# stacja_meteo_v3.net
KiCad netlist of a schematic drawn in EAGLE
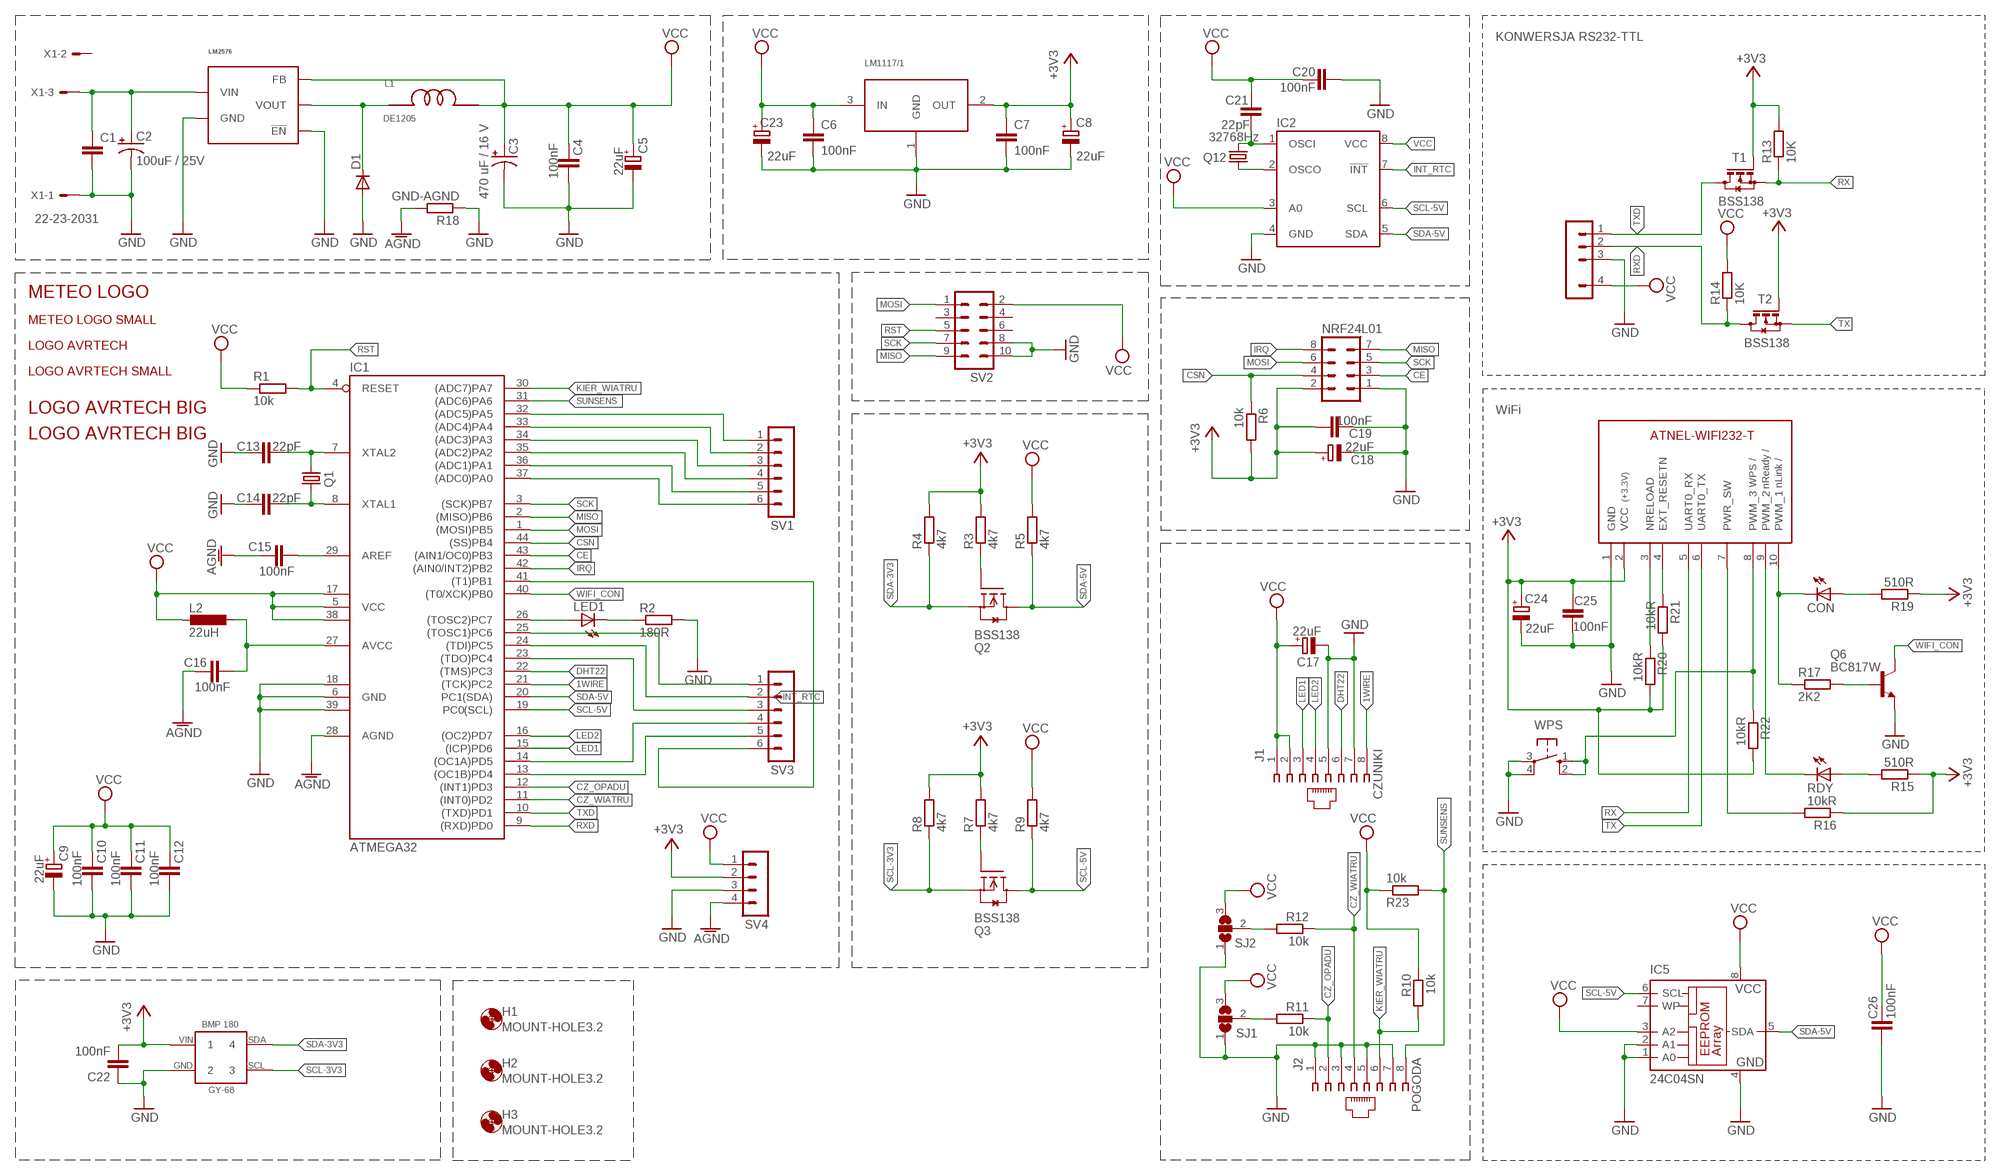
[diagram p0: schematic, sheet 1]

(export (version "E")
  (design (tool "Eeschema 10.0.6"))
  (components
    (comp (ref "BMP1")
      (value "GY-68")
      (footprint "eagle-import:GY-68")
      (libsource (lib "eagle-import") (part "GY-68"))
    )
    (comp (ref "C1")
      (value "C-EUC1206")
      (footprint "eagle-import:C1206")
      (libsource (lib "eagle-import") (part "C-EUC1206"))
    )
    (comp (ref "C2")
      (value "100uF / 25V")
      (footprint "eagle-import:PANASONIC_D")
      (libsource (lib "eagle-import") (part "CAP_POLD"))
    )
    (comp (ref "C3")
      (value "470 uF / 16 V")
      (footprint "eagle-import:PANASONIC_E")
      (libsource (lib "eagle-import") (part "CAP_POLE"))
    )
    (comp (ref "C4")
      (value "100nF")
      (footprint "eagle-import:C1206")
      (libsource (lib "eagle-import") (part "C-EUC1206"))
    )
    (comp (ref "C5")
      (value "22uF")
      (footprint "eagle-import:SMC_A")
      (libsource (lib "eagle-import") (part "CPOL-EUSMCA"))
    )
    (comp (ref "C6")
      (value "100nF")
      (footprint "eagle-import:C0805")
      (libsource (lib "eagle-import") (part "C-EUC0805"))
    )
    (comp (ref "C7")
      (value "100nF")
      (footprint "eagle-import:C0805")
      (libsource (lib "eagle-import") (part "C-EUC0805"))
    )
    (comp (ref "C8")
      (value "22uF")
      (footprint "eagle-import:SMC_A")
      (libsource (lib "eagle-import") (part "CPOL-EUSMCA"))
    )
    (comp (ref "C9")
      (value "22uF")
      (footprint "eagle-import:SMC_A")
      (libsource (lib "eagle-import") (part "CPOL-EUSMCA"))
    )
    (comp (ref "C10")
      (value "100nF")
      (footprint "eagle-import:C1206")
      (libsource (lib "eagle-import") (part "C-EUC1206"))
    )
    (comp (ref "C11")
      (value "100nF")
      (footprint "eagle-import:C1206")
      (libsource (lib "eagle-import") (part "C-EUC1206"))
    )
    (comp (ref "C12")
      (value "100nF")
      (footprint "eagle-import:C1206")
      (libsource (lib "eagle-import") (part "C-EUC1206"))
    )
    (comp (ref "C13")
      (value "22pF")
      (footprint "eagle-import:C0805K")
      (libsource (lib "eagle-import") (part "C-EUC0805K"))
    )
    (comp (ref "C14")
      (value "22pF")
      (footprint "eagle-import:C0805K")
      (libsource (lib "eagle-import") (part "C-EUC0805K"))
    )
    (comp (ref "C15")
      (value "100nF")
      (footprint "eagle-import:C1206")
      (libsource (lib "eagle-import") (part "C-EUC1206"))
    )
    (comp (ref "C16")
      (value "100nF")
      (footprint "eagle-import:C1206")
      (libsource (lib "eagle-import") (part "C-EUC1206"))
    )
    (comp (ref "C17")
      (value "22uF")
      (footprint "eagle-import:SMC_A")
      (libsource (lib "eagle-import") (part "CPOL-EUSMCA"))
    )
    (comp (ref "C18")
      (value "22uF")
      (footprint "eagle-import:SMC_A")
      (libsource (lib "eagle-import") (part "CPOL-EUSMCA"))
    )
    (comp (ref "C19")
      (value "100nF")
      (footprint "eagle-import:C0805")
      (libsource (lib "eagle-import") (part "C-EUC0805"))
    )
    (comp (ref "C20")
      (value "100nF")
      (footprint "eagle-import:C1206K")
      (libsource (lib "eagle-import") (part "C-EUC1206K"))
    )
    (comp (ref "C21")
      (value "22pF")
      (footprint "eagle-import:C1206K")
      (libsource (lib "eagle-import") (part "C-EUC1206K"))
    )
    (comp (ref "C22")
      (value "100nF")
      (footprint "eagle-import:C1206")
      (libsource (lib "eagle-import") (part "C-EUC1206"))
    )
    (comp (ref "C23")
      (value "22uF")
      (footprint "eagle-import:SMC_A")
      (libsource (lib "eagle-import") (part "CPOL-EUSMCA"))
    )
    (comp (ref "C24")
      (value "22uF")
      (footprint "eagle-import:SMC_A")
      (libsource (lib "eagle-import") (part "CPOL-EUSMCA"))
    )
    (comp (ref "C25")
      (value "100nF")
      (footprint "eagle-import:C0805")
      (libsource (lib "eagle-import") (part "C-EUC0805"))
    )
    (comp (ref "C26")
      (value "100nF")
      (footprint "eagle-import:C1206K")
      (libsource (lib "eagle-import") (part "C-EUC1206K"))
    )
    (comp (ref "CON")
      (value "LEDSML0805")
      (footprint "eagle-import:SML0805")
      (libsource (lib "eagle-import") (part "LEDSML0805"))
    )
    (comp (ref "D1")
      (value "DIODE-SMC")
      (footprint "eagle-import:SMC")
      (libsource (lib "eagle-import") (part "DIODE-SMC"))
    )
    (comp (ref "H1")
      (value "MOUNT-HOLE3.2")
      (footprint "eagle-import:3,2")
      (libsource (lib "eagle-import") (part "MOUNT-HOLE3.2"))
    )
    (comp (ref "H2")
      (value "MOUNT-HOLE3.2")
      (footprint "eagle-import:3,2")
      (libsource (lib "eagle-import") (part "MOUNT-HOLE3.2"))
    )
    (comp (ref "H3")
      (value "MOUNT-HOLE3.2")
      (footprint "eagle-import:3,2")
      (libsource (lib "eagle-import") (part "MOUNT-HOLE3.2"))
    )
    (comp (ref "IC1")
      (value "ATMEGA32")
      (footprint "eagle-import:TQFP44")
      (libsource (lib "eagle-import") (part "MEGA32ORIGINAL"))
    )
    (comp (ref "IC2")
      (value "RTC_PCF8583T")
      (footprint "eagle-import:SO08")
      (libsource (lib "eagle-import") (part "RTC_PCF8583T"))
    )
    (comp (ref "IC5")
      (value "24C04SN")
      (footprint "eagle-import:SO-08")
      (fields (field (name "MPN") "M24C04-WMN6P"))
      (libsource (lib "eagle-import") (part "24CSN04"))
    )
    (comp (ref "J1")
      (value "CZUNIKI")
      (footprint "eagle-import:556416-1")
      (libsource (lib "eagle-import") (part "556416-1"))
    )
    (comp (ref "J2")
      (value "POGODA")
      (footprint "eagle-import:556416-1")
      (libsource (lib "eagle-import") (part "556416-1"))
    )
    (comp (ref "L1")
      (value "DE1205")
      (footprint "eagle-import:DE1205")
      (libsource (lib "eagle-import") (part "DE1205"))
    )
    (comp (ref "L2")
      (value "22uH")
      (footprint "eagle-import:IR-2")
      (libsource (lib "eagle-import") (part "L-EUIR-2"))
    )
    (comp (ref "LED1")
      (value "LED5MM")
      (footprint "eagle-import:LED5MM")
      (libsource (lib "eagle-import") (part "LED5MM"))
    )
    (comp (ref "LM1117/1")
      (value "LM1117-3.3")
      (footprint "eagle-import:SOT223")
      (libsource (lib "eagle-import") (part "LM1117-3.3"))
    )
    (comp (ref "LM2576")
      (value "LM2576D2PAK-5")
      (footprint "eagle-import:D2PAK-5")
      (libsource (lib "eagle-import") (part "LM2576D2PAK-5"))
    )
    (comp (ref "NRF24L01")
      (value "ML10")
      (footprint "eagle-import:ML10")
      (libsource (lib "eagle-import") (part "ML10"))
    )
    (comp (ref "Q1")
      (value "11.059 MHz")
      (footprint "eagle-import:CSM-7X-DU")
      (libsource (lib "eagle-import") (part "CSM-7X-DU"))
    )
    (comp (ref "Q2")
      (value "BSS138")
      (footprint "eagle-import:SOT23")
      (libsource (lib "eagle-import") (part "BSS138"))
    )
    (comp (ref "Q3")
      (value "BSS138")
      (footprint "eagle-import:SOT23")
      (libsource (lib "eagle-import") (part "BSS138"))
    )
    (comp (ref "Q6")
      (value "BC817W")
      (footprint "eagle-import:SOT23-BEC")
      (libsource (lib "eagle-import") (part "BC817SMD-16LT1"))
    )
    (comp (ref "Q12")
      (value "32768Hz")
      (footprint "eagle-import:MC-406")
      (fields (field (name "MF") "BANNER ENGINEERING CORPORATION") (field (name "MPN") "MQDMC-406"))
      (libsource (lib "eagle-import") (part "MC-406"))
    )
    (comp (ref "R1")
      (value "10k")
      (footprint "eagle-import:R0603")
      (libsource (lib "eagle-import") (part "R-EU_R0603"))
    )
    (comp (ref "R2")
      (value "180R")
      (footprint "eagle-import:R0805")
      (libsource (lib "eagle-import") (part "R-EU_R0805"))
    )
    (comp (ref "R3")
      (value "4k7")
      (footprint "eagle-import:R0805")
      (libsource (lib "eagle-import") (part "R-EU_R0805"))
    )
    (comp (ref "R4")
      (value "4k7")
      (footprint "eagle-import:R0805")
      (libsource (lib "eagle-import") (part "R-EU_R0805"))
    )
    (comp (ref "R5")
      (value "4k7")
      (footprint "eagle-import:R0805")
      (libsource (lib "eagle-import") (part "R-EU_R0805"))
    )
    (comp (ref "R6")
      (value "10k")
      (footprint "eagle-import:R0805W")
      (libsource (lib "eagle-import") (part "R-EU_R0805W"))
    )
    (comp (ref "R7")
      (value "4k7")
      (footprint "eagle-import:R0805")
      (libsource (lib "eagle-import") (part "R-EU_R0805"))
    )
    (comp (ref "R8")
      (value "4k7")
      (footprint "eagle-import:R0805")
      (libsource (lib "eagle-import") (part "R-EU_R0805"))
    )
    (comp (ref "R9")
      (value "4k7")
      (footprint "eagle-import:R0805")
      (libsource (lib "eagle-import") (part "R-EU_R0805"))
    )
    (comp (ref "R10")
      (value "10k")
      (footprint "eagle-import:R0603")
      (libsource (lib "eagle-import") (part "R-EU_R0603"))
    )
    (comp (ref "R11")
      (value "10k")
      (footprint "eagle-import:R0603")
      (libsource (lib "eagle-import") (part "R-EU_R0603"))
    )
    (comp (ref "R12")
      (value "10k")
      (footprint "eagle-import:R0603")
      (libsource (lib "eagle-import") (part "R-EU_R0603"))
    )
    (comp (ref "R13")
      (value "10K")
      (footprint "eagle-import:R0805")
      (libsource (lib "eagle-import") (part "resistor_R-EU_R0805"))
    )
    (comp (ref "R14")
      (value "10K")
      (footprint "eagle-import:R0805")
      (libsource (lib "eagle-import") (part "resistor_R-EU_R0805"))
    )
    (comp (ref "R15")
      (value "510R")
      (footprint "eagle-import:R0603")
      (libsource (lib "eagle-import") (part "R-EU_R0603"))
    )
    (comp (ref "R16")
      (value "10kR")
      (footprint "eagle-import:R0603")
      (libsource (lib "eagle-import") (part "R-EU_R0603"))
    )
    (comp (ref "R17")
      (value "2K2")
      (footprint "eagle-import:R0603")
      (libsource (lib "eagle-import") (part "R-EU_R0603"))
    )
    (comp (ref "R18")
      (value "GND-AGND")
      (footprint "eagle-import:R0805")
      (libsource (lib "eagle-import") (part "R-EU_R0805"))
    )
    (comp (ref "R19")
      (value "510R")
      (footprint "eagle-import:R0603")
      (libsource (lib "eagle-import") (part "R-EU_R0603"))
    )
    (comp (ref "R20")
      (value "10kR")
      (footprint "eagle-import:R0603")
      (libsource (lib "eagle-import") (part "R-EU_R0603"))
    )
    (comp (ref "R21")
      (value "10kR")
      (footprint "eagle-import:R0603")
      (libsource (lib "eagle-import") (part "R-EU_R0603"))
    )
    (comp (ref "R22")
      (value "10kR")
      (footprint "eagle-import:R0603")
      (libsource (lib "eagle-import") (part "R-EU_R0603"))
    )
    (comp (ref "R23")
      (value "10k")
      (footprint "eagle-import:R0603")
      (libsource (lib "eagle-import") (part "R-EU_R0603"))
    )
    (comp (ref "RDY")
      (value "LEDSML0805")
      (footprint "eagle-import:SML0805")
      (libsource (lib "eagle-import") (part "LEDSML0805"))
    )
    (comp (ref "RS232-TTL")
      (value "ATB-BTM-222")
      (footprint "eagle-import:ATB-BTM-222")
      (libsource (lib "eagle-import") (part "ATB-BTM-222"))
    )
    (comp (ref "SJ1")
      (value "SJ2W")
      (footprint "eagle-import:SJ_2")
      (libsource (lib "eagle-import") (part "SJ2W"))
    )
    (comp (ref "SJ2")
      (value "SJ2W")
      (footprint "eagle-import:SJ_2")
      (libsource (lib "eagle-import") (part "SJ2W"))
    )
    (comp (ref "SV1")
      (value "MA06-1")
      (footprint "eagle-import:MA06-1")
      (libsource (lib "eagle-import") (part "MA06-1"))
    )
    (comp (ref "SV2")
      (value "ML10")
      (footprint "eagle-import:ML10")
      (libsource (lib "eagle-import") (part "con-harting-ml_ML10"))
    )
    (comp (ref "SV3")
      (value "MA06-1")
      (footprint "eagle-import:MA06-1")
      (libsource (lib "eagle-import") (part "MA06-1"))
    )
    (comp (ref "SV4")
      (value "MA04-1")
      (footprint "eagle-import:MA04-1")
      (libsource (lib "eagle-import") (part "MA04-1"))
    )
    (comp (ref "T1")
      (value "BSS138")
      (footprint "eagle-import:SOT23")
      (libsource (lib "eagle-import") (part "BSS123"))
    )
    (comp (ref "T2")
      (value "BSS138")
      (footprint "eagle-import:SOT23")
      (libsource (lib "eagle-import") (part "BSS123"))
    )
    (comp (ref "U$2")
      (value "ATNEL-WIFI232-T_2")
      (footprint "eagle-import:ATNEL-WIFI232-T_2")
      (libsource (lib "eagle-import") (part "ATNEL-WIFI232-T_2"))
    )
    (comp (ref "U$3")
      (value "METEO_LOGO")
      (footprint "eagle-import:LOGO_METEO")
      (libsource (lib "eagle-import") (part "METEO_LOGO"))
    )
    (comp (ref "U$4")
      (value "METEO_LOGO_SMALL")
      (footprint "eagle-import:LOGO_METEO_SMALL")
      (libsource (lib "eagle-import") (part "METEO_LOGO_SMALL"))
    )
    (comp (ref "U$6")
      (value "LOGO_AVRTECH")
      (footprint "eagle-import:LOGO_AVRTECH")
      (libsource (lib "eagle-import") (part "LOGO_AVRTECH"))
    )
    (comp (ref "U$7")
      (value "LOGO_AVRTECH_SMALL")
      (footprint "eagle-import:LOGO_AVRTECH_SMALL")
      (libsource (lib "eagle-import") (part "LOGO_AVRTECH_SMALL"))
    )
    (comp (ref "U$8")
      (value "LOGO_AVRTECH_BIG")
      (footprint "eagle-import:LOGOAVRTECHBIG")
      (libsource (lib "eagle-import") (part "LOGO_AVRTECH_BIG"))
    )
    (comp (ref "U$9")
      (value "LOGO_AVRTECH_BIG")
      (footprint "eagle-import:LOGOAVRTECHBIG")
      (libsource (lib "eagle-import") (part "LOGO_AVRTECH_BIG"))
    )
    (comp (ref "WPS")
      (value "10-XX")
      (footprint "eagle-import:B3F-10XX")
      (fields (field (name "MPN") "B3F-1000"))
      (libsource (lib "eagle-import") (part "10-XX"))
    )
    (comp (ref "X1")
      (value "22-23-2031")
      (footprint "eagle-import:22-23-2031")
      (fields (field (name "MF") "MOLEX"))
      (libsource (lib "eagle-import") (part "22-23-2031"))
    )
  )
  (nets
    (net (code "1") (name "+3V3") (class "Default")
      (node (ref "BMP1") (pin "1") (pinfunction "1_1") (pintype "bidirectional"))
      (node (ref "C18") (pin "+") (pinfunction "+_+") (pintype "passive"))
      (node (ref "C19") (pin "1") (pinfunction "1_1") (pintype "passive"))
      (node (ref "C22") (pin "2") (pinfunction "2_2") (pintype "passive"))
      (node (ref "C24") (pin "+") (pinfunction "+_+") (pintype "passive"))
      (node (ref "C25") (pin "1") (pinfunction "1_1") (pintype "passive"))
      (node (ref "C7") (pin "1") (pinfunction "1_1") (pintype "passive"))
      (node (ref "C8") (pin "+") (pinfunction "+_+") (pintype "passive"))
      (node (ref "LM1117/1") (pin "2") (pinfunction "OUT_2") (pintype "bidirectional"))
      (node (ref "NRF24L01") (pin "2") (pinfunction "2_2") (pintype "passive"))
      (node (ref "R13") (pin "2") (pinfunction "2_2") (pintype "passive"))
      (node (ref "R15") (pin "1") (pinfunction "1_1") (pintype "passive"))
      (node (ref "R16") (pin "1") (pinfunction "1_1") (pintype "passive"))
      (node (ref "R19") (pin "1") (pinfunction "1_1") (pintype "passive"))
      (node (ref "R20") (pin "2") (pinfunction "2_2") (pintype "passive"))
      (node (ref "R21") (pin "2") (pinfunction "2_2") (pintype "passive"))
      (node (ref "R22") (pin "2") (pinfunction "2_2") (pintype "passive"))
      (node (ref "R3") (pin "2") (pinfunction "2_2") (pintype "passive"))
      (node (ref "R4") (pin "2") (pinfunction "2_2") (pintype "passive"))
      (node (ref "R6") (pin "2") (pinfunction "2_2") (pintype "passive"))
      (node (ref "R7") (pin "2") (pinfunction "2_2") (pintype "passive"))
      (node (ref "R8") (pin "2") (pinfunction "2_2") (pintype "passive"))
      (node (ref "SV4") (pin "2") (pinfunction "2_2") (pintype "passive"))
      (node (ref "T1") (pin "1") (pinfunction "G_1") (pintype "passive"))
      (node (ref "T2") (pin "1") (pinfunction "G_1") (pintype "passive"))
      (node (ref "U$2") (pin "2") (pinfunction "VCC_2") (pintype "bidirectional"))
    )
    (net (code "2") (name "1WIRE") (class "Default")
      (node (ref "IC1") (pin "21") (pinfunction "(TCK)PC2_21") (pintype "bidirectional"))
      (node (ref "J1") (pin "8") (pinfunction "8_8") (pintype "passive"))
    )
    (net (code "3") (name "AGND") (class "Default")
      (node (ref "C15") (pin "1") (pinfunction "1_1") (pintype "passive"))
      (node (ref "C16") (pin "1") (pinfunction "1_1") (pintype "passive"))
      (node (ref "IC1") (pin "28") (pinfunction "AGND_28") (pintype "power_in"))
      (node (ref "R18") (pin "2") (pinfunction "2_2") (pintype "passive"))
      (node (ref "SV4") (pin "4") (pinfunction "4_4") (pintype "passive"))
    )
    (net (code "4") (name "CE") (class "Default")
      (node (ref "IC1") (pin "43") (pinfunction "(AIN1/OC0)PB3_43") (pintype "bidirectional"))
      (node (ref "NRF24L01") (pin "3") (pinfunction "3_3") (pintype "passive"))
    )
    (net (code "5") (name "CSN") (class "Default")
      (node (ref "IC1") (pin "44") (pinfunction "(SS)PB4_44") (pintype "bidirectional"))
      (node (ref "NRF24L01") (pin "4") (pinfunction "4_4") (pintype "passive"))
      (node (ref "R6") (pin "1") (pinfunction "1_1") (pintype "passive"))
    )
    (net (code "6") (name "CZ_OPADU") (class "Default")
      (node (ref "IC1") (pin "12") (pinfunction "(INT1)PD3_12") (pintype "bidirectional"))
      (node (ref "J2") (pin "2") (pinfunction "2_2") (pintype "passive"))
      (node (ref "R11") (pin "1") (pinfunction "1_1") (pintype "passive"))
    )
    (net (code "7") (name "CZ_WIATRU") (class "Default")
      (node (ref "IC1") (pin "11") (pinfunction "(INT0)PD2_11") (pintype "bidirectional"))
      (node (ref "J2") (pin "4") (pinfunction "4_4") (pintype "passive"))
      (node (ref "R12") (pin "1") (pinfunction "1_1") (pintype "passive"))
    )
    (net (code "8") (name "DHT22") (class "Default")
      (node (ref "IC1") (pin "22") (pinfunction "(TMS)PC3_22") (pintype "bidirectional"))
      (node (ref "J1") (pin "6") (pinfunction "6_6") (pintype "passive"))
    )
    (net (code "9") (name "GND") (class "Default")
      (node (ref "BMP1") (pin "2") (pinfunction "2_2") (pintype "bidirectional"))
      (node (ref "C1") (pin "2") (pinfunction "2_2") (pintype "passive"))
      (node (ref "C10") (pin "2") (pinfunction "2_2") (pintype "passive"))
      (node (ref "C11") (pin "2") (pinfunction "2_2") (pintype "passive"))
      (node (ref "C12") (pin "2") (pinfunction "2_2") (pintype "passive"))
      (node (ref "C13") (pin "1") (pinfunction "1_1") (pintype "passive"))
      (node (ref "C14") (pin "1") (pinfunction "1_1") (pintype "passive"))
      (node (ref "C17") (pin "-") (pinfunction "-_-") (pintype "passive"))
      (node (ref "C18") (pin "-") (pinfunction "-_-") (pintype "passive"))
      (node (ref "C19") (pin "2") (pinfunction "2_2") (pintype "passive"))
      (node (ref "C2") (pin "-") (pinfunction "-_-") (pintype "passive"))
      (node (ref "C20") (pin "2") (pinfunction "2_2") (pintype "passive"))
      (node (ref "C22") (pin "1") (pinfunction "1_1") (pintype "passive"))
      (node (ref "C23") (pin "-") (pinfunction "-_-") (pintype "passive"))
      (node (ref "C24") (pin "-") (pinfunction "-_-") (pintype "passive"))
      (node (ref "C25") (pin "2") (pinfunction "2_2") (pintype "passive"))
      (node (ref "C26") (pin "2") (pinfunction "2_2") (pintype "passive"))
      (node (ref "C3") (pin "-") (pinfunction "-_-") (pintype "passive"))
      (node (ref "C4") (pin "2") (pinfunction "2_2") (pintype "passive"))
      (node (ref "C5") (pin "-") (pinfunction "-_-") (pintype "passive"))
      (node (ref "C6") (pin "2") (pinfunction "2_2") (pintype "passive"))
      (node (ref "C7") (pin "2") (pinfunction "2_2") (pintype "passive"))
      (node (ref "C8") (pin "-") (pinfunction "-_-") (pintype "passive"))
      (node (ref "C9") (pin "-") (pinfunction "-_-") (pintype "passive"))
      (node (ref "D1") (pin "A") (pinfunction "A_A") (pintype "passive"))
      (node (ref "IC1") (pin "18") (pinfunction "GND1_18") (pintype "power_in"))
      (node (ref "IC1") (pin "39") (pinfunction "GND2_39") (pintype "power_in"))
      (node (ref "IC1") (pin "6") (pinfunction "GND_6") (pintype "power_in"))
      (node (ref "IC2") (pin "4") (pinfunction "GND_4") (pintype "power_in"))
      (node (ref "IC5") (pin "1") (pinfunction "A0_1") (pintype "input"))
      (node (ref "IC5") (pin "2") (pinfunction "A1_2") (pintype "input"))
      (node (ref "IC5") (pin "4") (pinfunction "GND_4") (pintype "power_in"))
      (node (ref "J1") (pin "5") (pinfunction "5_5") (pintype "passive"))
      (node (ref "J1") (pin "7") (pinfunction "7_7") (pintype "passive"))
      (node (ref "J2") (pin "1") (pinfunction "1_1") (pintype "passive"))
      (node (ref "J2") (pin "3") (pinfunction "3_3") (pintype "passive"))
      (node (ref "J2") (pin "5") (pinfunction "5_5") (pintype "passive"))
      (node (ref "J2") (pin "7") (pinfunction "7_7") (pintype "passive"))
      (node (ref "LM1117/1") (pin "1") (pinfunction "GND_1") (pintype "bidirectional"))
      (node (ref "LM2576") (pin "P$3") (pinfunction "GND_P$3") (pintype "bidirectional"))
      (node (ref "LM2576") (pin "P$5") (pinfunction "~{EN}_P$5") (pintype "bidirectional"))
      (node (ref "LM2576") (pin "P$6") (pinfunction "GND_P$6") (pintype "bidirectional"))
      (node (ref "NRF24L01") (pin "1") (pinfunction "1_1") (pintype "passive"))
      (node (ref "Q6") (pin "E") (pinfunction "E_E") (pintype "passive"))
      (node (ref "R18") (pin "1") (pinfunction "1_1") (pintype "passive"))
      (node (ref "R2") (pin "2") (pinfunction "2_2") (pintype "passive"))
      (node (ref "RS232-TTL") (pin "3") (pinfunction "GND_3") (pintype "passive"))
      (node (ref "SJ1") (pin "1") (pinfunction "1_1") (pintype "passive"))
      (node (ref "SJ2") (pin "1") (pinfunction "1_1") (pintype "passive"))
      (node (ref "SV2") (pin "10") (pinfunction "10_10") (pintype "passive"))
      (node (ref "SV2") (pin "8") (pinfunction "8_8") (pintype "passive"))
      (node (ref "SV4") (pin "3") (pinfunction "3_3") (pintype "passive"))
      (node (ref "U$2") (pin "1") (pinfunction "GND_1") (pintype "bidirectional"))
      (node (ref "WPS") (pin "3") (pinfunction "P_3") (pintype "passive"))
      (node (ref "WPS") (pin "4") (pinfunction "P1_4") (pintype "passive"))
      (node (ref "X1") (pin "1") (pinfunction "S_1") (pintype "passive"))
    )
    (net (code "10") (name "INT_RTC") (class "Default")
      (node (ref "IC1") (pin "24") (pinfunction "(TDI)PC5_24") (pintype "bidirectional"))
      (node (ref "IC2") (pin "7") (pinfunction "~{INT}_7") (pintype "output"))
      (node (ref "SV3") (pin "2") (pinfunction "2_2") (pintype "passive"))
    )
    (net (code "11") (name "IRQ") (class "Default")
      (node (ref "IC1") (pin "42") (pinfunction "(AIN0/INT2)PB2_42") (pintype "bidirectional"))
      (node (ref "NRF24L01") (pin "8") (pinfunction "8_8") (pintype "passive"))
    )
    (net (code "12") (name "KIER_WIATRU") (class "Default")
      (node (ref "IC1") (pin "30") (pinfunction "(ADC7)PA7_30") (pintype "bidirectional"))
      (node (ref "J2") (pin "6") (pinfunction "6_6") (pintype "passive"))
      (node (ref "R10") (pin "2") (pinfunction "2_2") (pintype "passive"))
    )
    (net (code "13") (name "LED1") (class "Default")
      (node (ref "IC1") (pin "15") (pinfunction "(ICP)PD6_15") (pintype "bidirectional"))
      (node (ref "J1") (pin "3") (pinfunction "3_3") (pintype "passive"))
    )
    (net (code "14") (name "LED2") (class "Default")
      (node (ref "IC1") (pin "16") (pinfunction "(OC2)PD7_16") (pintype "bidirectional"))
      (node (ref "J1") (pin "4") (pinfunction "4_4") (pintype "passive"))
    )
    (net (code "15") (name "MISO") (class "Default")
      (node (ref "IC1") (pin "2") (pinfunction "(MISO)PB6_2") (pintype "bidirectional"))
      (node (ref "NRF24L01") (pin "7") (pinfunction "7_7") (pintype "passive"))
      (node (ref "SV2") (pin "9") (pinfunction "9_9") (pintype "passive"))
    )
    (net (code "16") (name "MOSI") (class "Default")
      (node (ref "IC1") (pin "1") (pinfunction "(MOSI)PB5_1") (pintype "bidirectional"))
      (node (ref "NRF24L01") (pin "6") (pinfunction "6_6") (pintype "passive"))
      (node (ref "SV2") (pin "1") (pinfunction "1_1") (pintype "passive"))
    )
    (net (code "17") (name "Net-(CON-PadA)") (class "Default")
      (node (ref "CON") (pin "A") (pinfunction "A_A") (pintype "passive"))
      (node (ref "R19") (pin "2") (pinfunction "2_2") (pintype "passive"))
    )
    (net (code "18") (name "Net-(IC1-(ADC0)PA0)") (class "Default")
      (node (ref "IC1") (pin "37") (pinfunction "(ADC0)PA0_37") (pintype "bidirectional"))
      (node (ref "SV1") (pin "6") (pinfunction "6_6") (pintype "passive"))
    )
    (net (code "19") (name "Net-(IC1-(ADC1)PA1)") (class "Default")
      (node (ref "IC1") (pin "36") (pinfunction "(ADC1)PA1_36") (pintype "bidirectional"))
      (node (ref "SV1") (pin "5") (pinfunction "5_5") (pintype "passive"))
    )
    (net (code "20") (name "Net-(IC1-(ADC2)PA2)") (class "Default")
      (node (ref "IC1") (pin "35") (pinfunction "(ADC2)PA2_35") (pintype "bidirectional"))
      (node (ref "SV1") (pin "4") (pinfunction "4_4") (pintype "passive"))
    )
    (net (code "21") (name "Net-(IC1-(ADC3)PA3)") (class "Default")
      (node (ref "IC1") (pin "34") (pinfunction "(ADC3)PA3_34") (pintype "bidirectional"))
      (node (ref "SV1") (pin "3") (pinfunction "3_3") (pintype "passive"))
    )
    (net (code "22") (name "Net-(IC1-(ADC4)PA4)") (class "Default")
      (node (ref "IC1") (pin "33") (pinfunction "(ADC4)PA4_33") (pintype "bidirectional"))
      (node (ref "SV1") (pin "2") (pinfunction "2_2") (pintype "passive"))
    )
    (net (code "23") (name "Net-(IC1-(ADC5)PA5)") (class "Default")
      (node (ref "IC1") (pin "32") (pinfunction "(ADC5)PA5_32") (pintype "bidirectional"))
      (node (ref "SV1") (pin "1") (pinfunction "1_1") (pintype "passive"))
    )
    (net (code "24") (name "Net-(IC1-(OC1A)PD5)") (class "Default")
      (node (ref "IC1") (pin "14") (pinfunction "(OC1A)PD5_14") (pintype "bidirectional"))
      (node (ref "SV3") (pin "4") (pinfunction "4_4") (pintype "passive"))
    )
    (net (code "25") (name "Net-(IC1-(OC1B)PD4)") (class "Default")
      (node (ref "IC1") (pin "13") (pinfunction "(OC1B)PD4_13") (pintype "bidirectional"))
      (node (ref "SV3") (pin "5") (pinfunction "5_5") (pintype "passive"))
    )
    (net (code "26") (name "Net-(IC1-(T1)PB1)") (class "Default")
      (node (ref "IC1") (pin "41") (pinfunction "(T1)PB1_41") (pintype "bidirectional"))
      (node (ref "SV3") (pin "6") (pinfunction "6_6") (pintype "passive"))
    )
    (net (code "27") (name "Net-(IC1-(TDO)PC4)") (class "Default")
      (node (ref "IC1") (pin "23") (pinfunction "(TDO)PC4_23") (pintype "bidirectional"))
      (node (ref "SV3") (pin "3") (pinfunction "3_3") (pintype "passive"))
    )
    (net (code "28") (name "Net-(IC1-(TOSC1)PC6)") (class "Default")
      (node (ref "IC1") (pin "25") (pinfunction "(TOSC1)PC6_25") (pintype "bidirectional"))
      (node (ref "SV3") (pin "1") (pinfunction "1_1") (pintype "passive"))
    )
    (net (code "29") (name "Net-(IC1-(TOSC2)PC7)") (class "Default")
      (node (ref "IC1") (pin "26") (pinfunction "(TOSC2)PC7_26") (pintype "bidirectional"))
      (node (ref "LED1") (pin "A") (pinfunction "A_A") (pintype "passive"))
    )
    (net (code "30") (name "Net-(IC1-AREF)") (class "Default")
      (node (ref "C15") (pin "2") (pinfunction "2_2") (pintype "passive"))
      (node (ref "IC1") (pin "29") (pinfunction "AREF_29") (pintype "power_in"))
    )
    (net (code "31") (name "Net-(IC1-AVCC)") (class "Default")
      (node (ref "C16") (pin "2") (pinfunction "2_2") (pintype "passive"))
      (node (ref "IC1") (pin "27") (pinfunction "AVCC_27") (pintype "power_in"))
      (node (ref "L2") (pin "1") (pinfunction "1_1") (pintype "passive"))
    )
    (net (code "32") (name "Net-(IC1-XTAL1)") (class "Default")
      (node (ref "C14") (pin "2") (pinfunction "2_2") (pintype "passive"))
      (node (ref "IC1") (pin "8") (pinfunction "XTAL1_8") (pintype "bidirectional"))
      (node (ref "Q1") (pin "1") (pinfunction "1_1") (pintype "passive"))
    )
    (net (code "33") (name "Net-(IC1-XTAL2)") (class "Default")
      (node (ref "C13") (pin "2") (pinfunction "2_2") (pintype "passive"))
      (node (ref "IC1") (pin "7") (pinfunction "XTAL2_7") (pintype "bidirectional"))
      (node (ref "Q1") (pin "2") (pinfunction "2_2") (pintype "passive"))
    )
    (net (code "34") (name "Net-(IC2-OSCI)") (class "Default")
      (node (ref "C21") (pin "2") (pinfunction "2_2") (pintype "passive"))
      (node (ref "IC2") (pin "1") (pinfunction "OSCI_1") (pintype "input"))
      (node (ref "Q12") (pin "1") (pinfunction "1_1") (pintype "passive"))
    )
    (net (code "35") (name "Net-(IC2-OSCO)") (class "Default")
      (node (ref "IC2") (pin "2") (pinfunction "OSCO_2") (pintype "output"))
      (node (ref "Q12") (pin "2") (pinfunction "2_2") (pintype "passive"))
    )
    (net (code "36") (name "Net-(LED1-C)") (class "Default")
      (node (ref "LED1") (pin "K") (pinfunction "C_K") (pintype "passive"))
      (node (ref "R2") (pin "1") (pinfunction "1_1") (pintype "passive"))
    )
    (net (code "37") (name "Net-(LM2576-VIN)") (class "Default")
      (node (ref "C1") (pin "1") (pinfunction "1_1") (pintype "passive"))
      (node (ref "C2") (pin "+") (pinfunction "+_+") (pintype "passive"))
      (node (ref "LM2576") (pin "P$1") (pinfunction "VIN_P$1") (pintype "bidirectional"))
      (node (ref "X1") (pin "3") (pinfunction "S_3") (pintype "passive"))
    )
    (net (code "38") (name "Net-(LM2576-VOUT)") (class "Default")
      (node (ref "D1") (pin "C") (pinfunction "C_C") (pintype "passive"))
      (node (ref "L1") (pin "P$1") (pinfunction "P$1_P$1") (pintype "passive"))
      (node (ref "LM2576") (pin "P$2") (pinfunction "VOUT_P$2") (pintype "bidirectional"))
    )
    (net (code "39") (name "Net-(Q2-G)") (class "Default")
      (node (ref "Q2") (pin "1") (pinfunction "G_1") (pintype "passive"))
      (node (ref "R3") (pin "1") (pinfunction "1_1") (pintype "passive"))
    )
    (net (code "40") (name "Net-(Q3-G)") (class "Default")
      (node (ref "Q3") (pin "1") (pinfunction "G_1") (pintype "passive"))
      (node (ref "R7") (pin "1") (pinfunction "1_1") (pintype "passive"))
    )
    (net (code "41") (name "Net-(Q6-PadB)") (class "Default")
      (node (ref "Q6") (pin "B") (pinfunction "B_B") (pintype "passive"))
      (node (ref "R17") (pin "2") (pinfunction "2_2") (pintype "passive"))
    )
    (net (code "42") (name "Net-(R11-Pad2)") (class "Default")
      (node (ref "R11") (pin "2") (pinfunction "2_2") (pintype "passive"))
      (node (ref "SJ1") (pin "2") (pinfunction "2_2") (pintype "passive"))
    )
    (net (code "43") (name "Net-(R12-Pad2)") (class "Default")
      (node (ref "R12") (pin "2") (pinfunction "2_2") (pintype "passive"))
      (node (ref "SJ2") (pin "2") (pinfunction "2_2") (pintype "passive"))
    )
    (net (code "44") (name "Net-(R15-Pad2)") (class "Default")
      (node (ref "R15") (pin "2") (pinfunction "2_2") (pintype "passive"))
      (node (ref "RDY") (pin "A") (pinfunction "A_A") (pintype "passive"))
    )
    (net (code "45") (name "Net-(U$2-EXT_RESETN)") (class "Default")
      (node (ref "R21") (pin "1") (pinfunction "1_1") (pintype "passive"))
      (node (ref "U$2") (pin "4") (pinfunction "EXT_RESETN_4") (pintype "input"))
    )
    (net (code "46") (name "Net-(U$2-NRELOAD)") (class "Default")
      (node (ref "R20") (pin "1") (pinfunction "1_1") (pintype "passive"))
      (node (ref "U$2") (pin "3") (pinfunction "NRELOAD_3") (pintype "input"))
    )
    (net (code "47") (name "Net-(U$2-PWM_1)") (class "Default")
      (node (ref "CON") (pin "C") (pinfunction "C_C") (pintype "passive"))
      (node (ref "R17") (pin "1") (pinfunction "1_1") (pintype "passive"))
      (node (ref "U$2") (pin "10") (pinfunction "PWM_1_10") (pintype "bidirectional"))
    )
    (net (code "48") (name "Net-(U$2-PWM_2)") (class "Default")
      (node (ref "RDY") (pin "C") (pinfunction "C_C") (pintype "passive"))
      (node (ref "U$2") (pin "9") (pinfunction "PWM_2_9") (pintype "bidirectional"))
    )
    (net (code "49") (name "Net-(U$2-PWM_3)") (class "Default")
      (node (ref "R22") (pin "1") (pinfunction "1_1") (pintype "passive"))
      (node (ref "U$2") (pin "8") (pinfunction "PWM_3_8") (pintype "bidirectional"))
      (node (ref "WPS") (pin "1") (pinfunction "S_1") (pintype "passive"))
      (node (ref "WPS") (pin "2") (pinfunction "S1_2") (pintype "passive"))
    )
    (net (code "50") (name "Net-(U$2-PWR_SW)") (class "Default")
      (node (ref "R16") (pin "2") (pinfunction "2_2") (pintype "passive"))
      (node (ref "U$2") (pin "7") (pinfunction "PWR_SW_7") (pintype "input"))
    )
    (net (code "51") (name "RST") (class "Default")
      (node (ref "IC1") (pin "4") (pinfunction "RESET_4") (pintype "input"))
      (node (ref "R1") (pin "2") (pinfunction "2_2") (pintype "passive"))
      (node (ref "SV2") (pin "5") (pinfunction "5_5") (pintype "passive"))
    )
    (net (code "52") (name "RX") (class "Default")
      (node (ref "R13") (pin "1") (pinfunction "1_1") (pintype "passive"))
      (node (ref "T1") (pin "2") (pinfunction "S_2") (pintype "passive"))
      (node (ref "U$2") (pin "5") (pinfunction "UART0_RX_5") (pintype "input"))
    )
    (net (code "53") (name "RXD") (class "Default")
      (node (ref "IC1") (pin "9") (pinfunction "(RXD)PD0_9") (pintype "bidirectional"))
      (node (ref "R14") (pin "1") (pinfunction "1_1") (pintype "passive"))
      (node (ref "RS232-TTL") (pin "2") (pinfunction "TX_2") (pintype "passive"))
      (node (ref "T2") (pin "3") (pinfunction "D_3") (pintype "passive"))
    )
    (net (code "54") (name "SCK") (class "Default")
      (node (ref "IC1") (pin "3") (pinfunction "(SCK)PB7_3") (pintype "bidirectional"))
      (node (ref "NRF24L01") (pin "5") (pinfunction "5_5") (pintype "passive"))
      (node (ref "SV2") (pin "7") (pinfunction "7_7") (pintype "passive"))
    )
    (net (code "55") (name "SCL-3V3") (class "Default")
      (node (ref "BMP1") (pin "3") (pinfunction "3_3") (pintype "bidirectional"))
      (node (ref "Q3") (pin "2") (pinfunction "S_2") (pintype "passive"))
      (node (ref "R8") (pin "1") (pinfunction "1_1") (pintype "passive"))
    )
    (net (code "56") (name "SCL-5V") (class "Default")
      (node (ref "IC1") (pin "19") (pinfunction "PC0(SCL)_19") (pintype "bidirectional"))
      (node (ref "IC2") (pin "6") (pinfunction "SCL_6") (pintype "input"))
      (node (ref "IC5") (pin "6") (pinfunction "SCL_6") (pintype "input"))
      (node (ref "Q3") (pin "3") (pinfunction "D_3") (pintype "passive"))
      (node (ref "R9") (pin "1") (pinfunction "1_1") (pintype "passive"))
    )
    (net (code "57") (name "SDA-3V3") (class "Default")
      (node (ref "BMP1") (pin "4") (pinfunction "4_4") (pintype "bidirectional"))
      (node (ref "Q2") (pin "2") (pinfunction "S_2") (pintype "passive"))
      (node (ref "R4") (pin "1") (pinfunction "1_1") (pintype "passive"))
    )
    (net (code "58") (name "SDA-5V") (class "Default")
      (node (ref "IC1") (pin "20") (pinfunction "PC1(SDA)_20") (pintype "bidirectional"))
      (node (ref "IC2") (pin "5") (pinfunction "SDA_5") (pintype "bidirectional"))
      (node (ref "IC5") (pin "5") (pinfunction "SDA_5") (pintype "bidirectional"))
      (node (ref "Q2") (pin "3") (pinfunction "D_3") (pintype "passive"))
      (node (ref "R5") (pin "1") (pinfunction "1_1") (pintype "passive"))
    )
    (net (code "59") (name "SUNSENS") (class "Default")
      (node (ref "IC1") (pin "31") (pinfunction "(ADC6)PA6_31") (pintype "bidirectional"))
      (node (ref "J2") (pin "8") (pinfunction "8_8") (pintype "passive"))
      (node (ref "R23") (pin "2") (pinfunction "2_2") (pintype "passive"))
    )
    (net (code "60") (name "TX") (class "Default")
      (node (ref "T2") (pin "2") (pinfunction "S_2") (pintype "passive"))
      (node (ref "U$2") (pin "6") (pinfunction "UART0_TX_6") (pintype "output"))
    )
    (net (code "61") (name "TXD") (class "Default")
      (node (ref "IC1") (pin "10") (pinfunction "(TXD)PD1_10") (pintype "bidirectional"))
      (node (ref "RS232-TTL") (pin "1") (pinfunction "RX_1") (pintype "passive"))
      (node (ref "T1") (pin "3") (pinfunction "D_3") (pintype "passive"))
    )
    (net (code "62") (name "VCC") (class "Default")
      (node (ref "C10") (pin "1") (pinfunction "1_1") (pintype "passive"))
      (node (ref "C11") (pin "1") (pinfunction "1_1") (pintype "passive"))
      (node (ref "C12") (pin "1") (pinfunction "1_1") (pintype "passive"))
      (node (ref "C17") (pin "+") (pinfunction "+_+") (pintype "passive"))
      (node (ref "C20") (pin "1") (pinfunction "1_1") (pintype "passive"))
      (node (ref "C21") (pin "1") (pinfunction "1_1") (pintype "passive"))
      (node (ref "C23") (pin "+") (pinfunction "+_+") (pintype "passive"))
      (node (ref "C26") (pin "1") (pinfunction "1_1") (pintype "passive"))
      (node (ref "C3") (pin "+") (pinfunction "+_+") (pintype "passive"))
      (node (ref "C4") (pin "1") (pinfunction "1_1") (pintype "passive"))
      (node (ref "C5") (pin "+") (pinfunction "+_+") (pintype "passive"))
      (node (ref "C6") (pin "1") (pinfunction "1_1") (pintype "passive"))
      (node (ref "C9") (pin "+") (pinfunction "+_+") (pintype "passive"))
      (node (ref "IC1") (pin "17") (pinfunction "VCC1_17") (pintype "power_in"))
      (node (ref "IC1") (pin "38") (pinfunction "VCC2_38") (pintype "power_in"))
      (node (ref "IC1") (pin "5") (pinfunction "VCC_5") (pintype "power_in"))
      (node (ref "IC2") (pin "3") (pinfunction "A0_3") (pintype "input"))
      (node (ref "IC2") (pin "8") (pinfunction "VCC_8") (pintype "power_in"))
      (node (ref "IC5") (pin "3") (pinfunction "A2_3") (pintype "input"))
      (node (ref "IC5") (pin "8") (pinfunction "VCC_8") (pintype "power_in"))
      (node (ref "J1") (pin "1") (pinfunction "1_1") (pintype "passive"))
      (node (ref "J1") (pin "2") (pinfunction "2_2") (pintype "passive"))
      (node (ref "L1") (pin "P$3") (pinfunction "P$2_P$3") (pintype "passive"))
      (node (ref "L2") (pin "2") (pinfunction "2_2") (pintype "passive"))
      (node (ref "LM1117/1") (pin "3") (pinfunction "IN_3") (pintype "bidirectional"))
      (node (ref "LM2576") (pin "P$4") (pinfunction "FB_P$4") (pintype "bidirectional"))
      (node (ref "R1") (pin "1") (pinfunction "1_1") (pintype "passive"))
      (node (ref "R10") (pin "1") (pinfunction "1_1") (pintype "passive"))
      (node (ref "R14") (pin "2") (pinfunction "2_2") (pintype "passive"))
      (node (ref "R23") (pin "1") (pinfunction "1_1") (pintype "passive"))
      (node (ref "R5") (pin "2") (pinfunction "2_2") (pintype "passive"))
      (node (ref "R9") (pin "2") (pinfunction "2_2") (pintype "passive"))
      (node (ref "RS232-TTL") (pin "4") (pinfunction "VCC_4") (pintype "passive"))
      (node (ref "SJ1") (pin "3") (pinfunction "3_3") (pintype "passive"))
      (node (ref "SJ2") (pin "3") (pinfunction "3_3") (pintype "passive"))
      (node (ref "SV2") (pin "2") (pinfunction "2_2") (pintype "passive"))
      (node (ref "SV4") (pin "1") (pinfunction "1_1") (pintype "passive"))
    )
    (net (code "63") (name "WIFI_CON") (class "Default")
      (node (ref "IC1") (pin "40") (pinfunction "(T0/XCK)PB0_40") (pintype "bidirectional"))
      (node (ref "Q6") (pin "C") (pinfunction "C_C") (pintype "passive"))
    )
    (net (code "64") (name "unconnected-(IC5-WP-Pad7)") (class "Default")
      (node (ref "IC5") (pin "7") (pinfunction "WP_7") (pintype "input"))
    )
    (net (code "65") (name "unconnected-(SV2-Pad3)") (class "Default")
      (node (ref "SV2") (pin "3") (pinfunction "3_3") (pintype "passive"))
    )
    (net (code "66") (name "unconnected-(SV2-Pad4)") (class "Default")
      (node (ref "SV2") (pin "4") (pinfunction "4_4") (pintype "passive"))
    )
    (net (code "67") (name "unconnected-(SV2-Pad6)") (class "Default")
      (node (ref "SV2") (pin "6") (pinfunction "6_6") (pintype "passive"))
    )
    (net (code "68") (name "unconnected-(X1B-S-Pad2)") (class "Default")
      (node (ref "X1") (pin "2") (pinfunction "S_2") (pintype "passive"))
    )
  )
)
